# IOTLoRaSmartGreenhouseGateway.net
KiCad netlist of a schematic drawn in Altium Designer
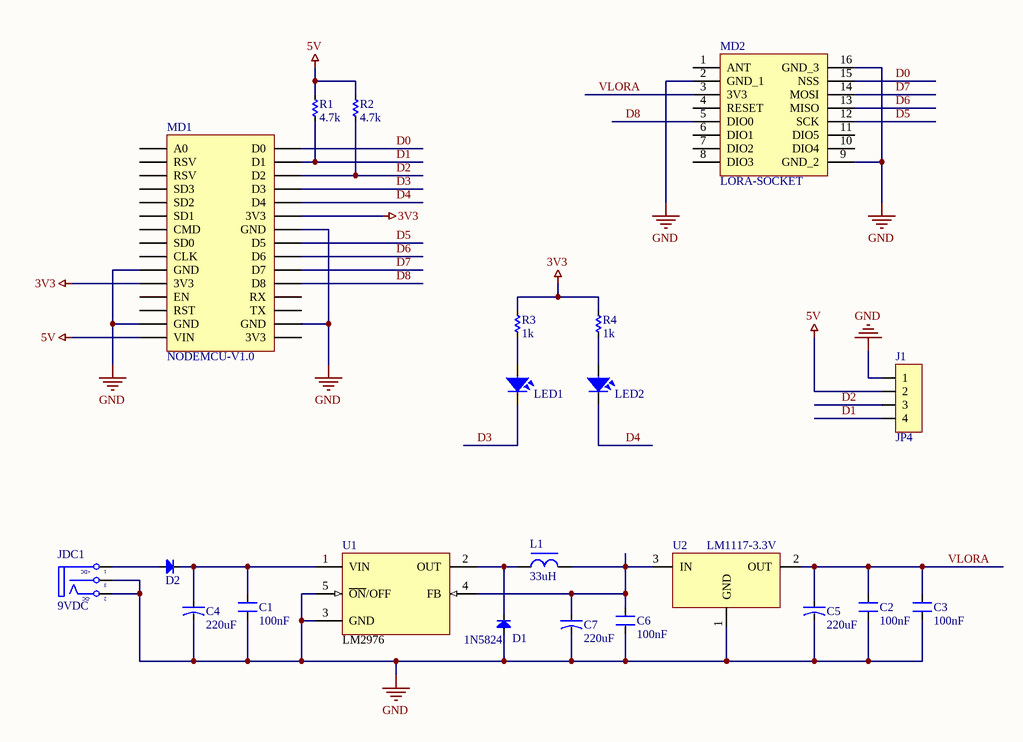
[diagram p0: IOTLoRaSmartGreenhouseGateway.SchDoc]

(export (version "E")
  (design (tool "Eeschema 10.0.6"))
  (components
    (comp (ref "C1") (value "100nF") (footprint "CN1.5") (libsource (lib "LIBRARY") (part "CN")))
    (comp (ref "C2") (value "100nF") (footprint "CN1.5") (libsource (lib "LIBRARY") (part "CN")))
    (comp (ref "C3") (value "100nF") (footprint "CN1.5") (libsource (lib "LIBRARY") (part "CN")))
    (comp (ref "C4")
      (value "220uF")
      (footprint "CA-ALU-8")
      (description "Capacitor (Semiconductor SIM Model)")
      (fields (field (name "PUBLISHER") "Altium Limited"))
      (libsource (lib "LIBRARY") (part "CN-ALU-DIP"))
    )
    (comp (ref "C5")
      (value "220uF")
      (footprint "CA-ALU-8")
      (description "Capacitor (Semiconductor SIM Model)")
      (fields (field (name "PUBLISHER") "Altium Limited"))
      (libsource (lib "LIBRARY") (part "CN-ALU-DIP"))
    )
    (comp (ref "C6") (value "100nF") (footprint "CN1.5") (libsource (lib "LIBRARY") (part "CN")))
    (comp (ref "C7")
      (value "220uF")
      (footprint "CA-ALU-8")
      (description "Capacitor (Semiconductor SIM Model)")
      (fields (field (name "PUBLISHER") "Altium Limited"))
      (libsource (lib "LIBRARY") (part "CN-ALU-DIP"))
    )
    (comp (ref "D1")
      (value "1N5824")
      (footprint "DIO-5A")
      (description "Default Diode")
      (fields (field (name "PUBLISHER") "Altium Limited"))
      (libsource (lib "LIBRARY") (part "Diode"))
    )
    (comp (ref "D2")
      (value "Diode")
      (footprint "DIO-3A")
      (description "Default Diode")
      (fields (field (name "PUBLISHER") "Altium Limited"))
      (libsource (lib "LIBRARY") (part "Diode"))
    )
    (comp (ref "J1")
      (value "JP4")
      (footprint "JP4-D1C")
      (description "WR-PHD 2.54 mm Angled Socket Header")
      (fields
        (field (name "MANUFACTURER") "Würth Elektronik eiSos GmbH")
        (field (name "PARTNO") "613004143121")
        (field (name "CREATED BY") "Karrer Zheng")
      )
      (libsource (lib "LIBRARY") (part "JP4"))
    )
    (comp (ref "JDC1")
      (value "9VDC")
      (footprint "DC0")
      (description "Jac DC input")
      (libsource (lib "LIBRARY") (part "DCIN"))
    )
    (comp (ref "L1")
      (value "33uH")
      (footprint "L-DIP-M-10")
      (description "Inductor")
      (libsource (lib "LIBRARY") (part "L-DIP-1"))
    )
    (comp (ref "LED1")
      (value "LED")
      (footprint "LED-3MM-BLUE")
      (description "LED Single colour Green and Red")
      (libsource (lib "LIBRARY") (part "LED"))
    )
    (comp (ref "LED2")
      (value "LED")
      (footprint "LED-3MM-BLUE")
      (description "LED Single colour Green and Red")
      (libsource (lib "LIBRARY") (part "LED"))
    )
    (comp (ref "MD1")
      (value "NODEMCU-V1.0")
      (footprint "NODEMCU-V1.0")
      (description "KIT NodeMCU v1.0")
      (libsource (lib "phatvu1294_Lib") (part "NODEMCU-V1.0"))
    )
    (comp (ref "MD2")
      (value "LORA-SOCKET")
      (footprint "LORA-SOCKET")
      (description "Socket LoRa RA01 va RA02")
      (libsource (lib "User") (part "LORA-SOCKET"))
    )
    (comp (ref "R1")
      (value "4.7k")
      (footprint "RES-1/4W")
      (description "Res")
      (fields
        (field (name "MANUFACTURER") "Generic Components")
        (field (name "PUBLISHER") "Altium Hobart Technology Centre")
      )
      (libsource (lib "LIBRARY") (part "Res"))
    )
    (comp (ref "R2")
      (value "4.7k")
      (footprint "RES-1/4W")
      (description "Res")
      (fields
        (field (name "MANUFACTURER") "Generic Components")
        (field (name "PUBLISHER") "Altium Hobart Technology Centre")
      )
      (libsource (lib "LIBRARY") (part "Res"))
    )
    (comp (ref "R3")
      (value "1k")
      (footprint "RES-1/4W")
      (description "Res")
      (fields
        (field (name "MANUFACTURER") "Generic Components")
        (field (name "PUBLISHER") "Altium Hobart Technology Centre")
      )
      (libsource (lib "LIBRARY") (part "Res"))
    )
    (comp (ref "R4")
      (value "1k")
      (footprint "RES-1/4W")
      (description "Res")
      (fields
        (field (name "MANUFACTURER") "Generic Components")
        (field (name "PUBLISHER") "Altium Hobart Technology Centre")
      )
      (libsource (lib "LIBRARY") (part "Res"))
    )
    (comp (ref "U1") (value "LM2976") (footprint "TO263") (libsource (lib "LIBRARY") (part "LM2596")))
    (comp (ref "U2")
      (value "LM1117-3.3V")
      (footprint "SOT223")
      (description "800mA Low-Dropout Linear Regulator")
      (fields (field (name "CREATOR") "Nguyen Ba Bien"))
      (libsource (lib "LIBRARY") (part "LM1117"))
    )
  )
  (nets
    (net (code "1") (name "/D0") (class "Default")
      (node (ref "MD1") (pin "D0") (pinfunction "D0_D0") (pintype "passive"))
      (node (ref "MD2") (pin "15") (pinfunction "NSS_15") (pintype "passive"))
    )
    (net (code "2") (name "/D1") (class "Default")
      (node (ref "J1") (pin "4") (pinfunction "4_4") (pintype "passive"))
      (node (ref "MD1") (pin "D1") (pinfunction "D1_D1") (pintype "passive"))
      (node (ref "R1") (pin "2") (pinfunction "2_2") (pintype "passive"))
    )
    (net (code "3") (name "/D2") (class "Default")
      (node (ref "J1") (pin "3") (pinfunction "3_3") (pintype "passive"))
      (node (ref "MD1") (pin "D2") (pinfunction "D2_D2") (pintype "passive"))
      (node (ref "R2") (pin "2") (pinfunction "2_2") (pintype "passive"))
    )
    (net (code "4") (name "/D3") (class "Default")
      (node (ref "LED1") (pin "2") (pinfunction "2_2") (pintype "passive"))
      (node (ref "MD1") (pin "D3") (pinfunction "D3_D3") (pintype "passive"))
    )
    (net (code "5") (name "/D4") (class "Default")
      (node (ref "LED2") (pin "2") (pinfunction "2_2") (pintype "passive"))
      (node (ref "MD1") (pin "D4") (pinfunction "D4_D4") (pintype "passive"))
    )
    (net (code "6") (name "/D5") (class "Default")
      (node (ref "MD1") (pin "D5") (pinfunction "D5_D5") (pintype "passive"))
      (node (ref "MD2") (pin "12") (pinfunction "SCK_12") (pintype "passive"))
    )
    (net (code "7") (name "/D6") (class "Default")
      (node (ref "MD1") (pin "D6") (pinfunction "D6_D6") (pintype "passive"))
      (node (ref "MD2") (pin "13") (pinfunction "MISO_13") (pintype "passive"))
    )
    (net (code "8") (name "/D7") (class "Default")
      (node (ref "MD1") (pin "D7") (pinfunction "D7_D7") (pintype "passive"))
      (node (ref "MD2") (pin "14") (pinfunction "MOSI_14") (pintype "passive"))
    )
    (net (code "9") (name "/D8") (class "Default")
      (node (ref "MD1") (pin "D8") (pinfunction "D8_D8") (pintype "passive"))
      (node (ref "MD2") (pin "5") (pinfunction "DIO0_5") (pintype "passive"))
    )
    (net (code "10") (name "/VLORA") (class "Default")
      (node (ref "C2") (pin "1") (pinfunction "1_1") (pintype "passive"))
      (node (ref "C3") (pin "1") (pinfunction "1_1") (pintype "passive"))
      (node (ref "C5") (pin "1") (pinfunction "1_1") (pintype "passive"))
      (node (ref "MD2") (pin "3") (pinfunction "3V3_3") (pintype "passive"))
      (node (ref "U2") (pin "2") (pinfunction "OUT_2") (pintype "passive"))
    )
    (net (code "11") (name "3V3") (class "Default")
      (node (ref "MD1") (pin "3V3") (pinfunction "3V3_3V3") (pintype "power_in"))
      (node (ref "R3") (pin "1") (pinfunction "1_1") (pintype "passive"))
      (node (ref "R4") (pin "1") (pinfunction "1_1") (pintype "passive"))
    )
    (net (code "12") (name "5V") (class "Default")
      (node (ref "J1") (pin "2") (pinfunction "2_2") (pintype "passive"))
      (node (ref "MD1") (pin "VIN") (pinfunction "VIN_VIN") (pintype "power_in"))
      (node (ref "R1") (pin "1") (pinfunction "1_1") (pintype "passive"))
      (node (ref "R2") (pin "1") (pinfunction "1_1") (pintype "passive"))
    )
    (net (code "13") (name "GND") (class "Default")
      (node (ref "C1") (pin "2") (pinfunction "2_2") (pintype "passive"))
      (node (ref "C2") (pin "2") (pinfunction "2_2") (pintype "passive"))
      (node (ref "C3") (pin "2") (pinfunction "2_2") (pintype "passive"))
      (node (ref "C4") (pin "2") (pinfunction "2_2") (pintype "passive"))
      (node (ref "C5") (pin "2") (pinfunction "2_2") (pintype "passive"))
      (node (ref "C6") (pin "2") (pinfunction "2_2") (pintype "passive"))
      (node (ref "C7") (pin "2") (pinfunction "2_2") (pintype "passive"))
      (node (ref "D1") (pin "1") (pinfunction "A_1") (pintype "passive"))
      (node (ref "J1") (pin "1") (pinfunction "1_1") (pintype "passive"))
      (node (ref "JDC1") (pin "2") (pinfunction "TN_2") (pintype "passive"))
      (node (ref "JDC1") (pin "3") (pinfunction "S_3") (pintype "power_in"))
      (node (ref "MD1") (pin "GND") (pinfunction "GND_GND") (pintype "power_in"))
      (node (ref "MD2") (pin "16") (pinfunction "GND_3_16") (pintype "passive"))
      (node (ref "MD2") (pin "2") (pinfunction "GND_1_2") (pintype "passive"))
      (node (ref "MD2") (pin "9") (pinfunction "GND_2_9") (pintype "passive"))
      (node (ref "U1") (pin "3") (pinfunction "GND_3") (pintype "power_in"))
      (node (ref "U1") (pin "5") (pinfunction "~{ON}/OFF_5") (pintype "input"))
      (node (ref "U2") (pin "1") (pinfunction "GND_1") (pintype "passive"))
    )
    (net (code "14") (name "Net-(D1-K)") (class "Default")
      (node (ref "D1") (pin "2") (pinfunction "K_2") (pintype "passive"))
      (node (ref "L1") (pin "1") (pinfunction "1_1") (pintype "passive"))
      (node (ref "U1") (pin "2") (pinfunction "OUT_2") (pintype "power_in"))
    )
    (net (code "15") (name "Net-(D2-A)") (class "Default")
      (node (ref "D2") (pin "1") (pinfunction "A_1") (pintype "passive"))
      (node (ref "JDC1") (pin "1") (pinfunction "T_1") (pintype "passive"))
    )
    (net (code "16") (name "Net-(D2-K)") (class "Default")
      (node (ref "C1") (pin "1") (pinfunction "1_1") (pintype "passive"))
      (node (ref "C4") (pin "1") (pinfunction "1_1") (pintype "passive"))
      (node (ref "D2") (pin "2") (pinfunction "K_2") (pintype "passive"))
      (node (ref "U1") (pin "1") (pinfunction "VIN_1") (pintype "power_in"))
    )
    (net (code "17") (name "Net-(LED1-Pad1)") (class "Default")
      (node (ref "LED1") (pin "1") (pinfunction "1_1") (pintype "passive"))
      (node (ref "R3") (pin "2") (pinfunction "2_2") (pintype "passive"))
    )
    (net (code "18") (name "Net-(LED2-Pad1)") (class "Default")
      (node (ref "LED2") (pin "1") (pinfunction "1_1") (pintype "passive"))
      (node (ref "R4") (pin "2") (pinfunction "2_2") (pintype "passive"))
    )
    (net (code "19") (name "Net-(U1-FB)") (class "Default")
      (node (ref "C6") (pin "1") (pinfunction "1_1") (pintype "passive"))
      (node (ref "C7") (pin "1") (pinfunction "1_1") (pintype "passive"))
      (node (ref "L1") (pin "2") (pinfunction "2_2") (pintype "passive"))
      (node (ref "U1") (pin "4") (pinfunction "FB_4") (pintype "input"))
      (node (ref "U2") (pin "3") (pinfunction "IN_3") (pintype "passive"))
    )
    (net (code "20") (name "unconnected-(MD1-Pad3V3)") (class "Default")
      (node (ref "MD1") (pin "3V3") (pinfunction "3V3_3V3") (pintype "power_in"))
    )
    (net (code "21") (name "unconnected-(MD1-PadA0)") (class "Default")
      (node (ref "MD1") (pin "A0") (pinfunction "A0_A0") (pintype "passive"))
    )
    (net (code "22") (name "unconnected-(MD1-PadCLK)") (class "Default")
      (node (ref "MD1") (pin "CLK") (pinfunction "CLK_CLK") (pintype "passive"))
    )
    (net (code "23") (name "unconnected-(MD1-PadCMD)") (class "Default")
      (node (ref "MD1") (pin "CMD") (pinfunction "CMD_CMD") (pintype "passive"))
    )
    (net (code "24") (name "unconnected-(MD1-PadEN)") (class "Default")
      (node (ref "MD1") (pin "EN") (pinfunction "EN_EN") (pintype "passive"))
    )
    (net (code "25") (name "unconnected-(MD1-PadRST)") (class "Default")
      (node (ref "MD1") (pin "RST") (pinfunction "RST_RST") (pintype "passive"))
    )
    (net (code "26") (name "unconnected-(MD1-PadRSV)") (class "Default")
      (node (ref "MD1") (pin "RSV") (pinfunction "RSV_RSV") (pintype "passive"))
    )
    (net (code "27") (name "unconnected-(MD1-PadRSV)_1") (class "Default")
      (node (ref "MD1") (pin "RSV") (pinfunction "RSV_RSV") (pintype "passive"))
    )
    (net (code "28") (name "unconnected-(MD1-PadRX)") (class "Default")
      (node (ref "MD1") (pin "RX") (pinfunction "RX_RX") (pintype "passive"))
    )
    (net (code "29") (name "unconnected-(MD1-PadSD0)") (class "Default")
      (node (ref "MD1") (pin "SD0") (pinfunction "SD0_SD0") (pintype "passive"))
    )
    (net (code "30") (name "unconnected-(MD1-PadSD1)") (class "Default")
      (node (ref "MD1") (pin "SD1") (pinfunction "SD1_SD1") (pintype "passive"))
    )
    (net (code "31") (name "unconnected-(MD1-PadSD2)") (class "Default")
      (node (ref "MD1") (pin "SD2") (pinfunction "SD2_SD2") (pintype "passive"))
    )
    (net (code "32") (name "unconnected-(MD1-PadSD3)") (class "Default")
      (node (ref "MD1") (pin "SD3") (pinfunction "SD3_SD3") (pintype "passive"))
    )
    (net (code "33") (name "unconnected-(MD1-PadTX)") (class "Default")
      (node (ref "MD1") (pin "TX") (pinfunction "TX_TX") (pintype "passive"))
    )
    (net (code "34") (name "unconnected-(MD2-ANT-Pad1)") (class "Default")
      (node (ref "MD2") (pin "1") (pinfunction "ANT_1") (pintype "passive"))
    )
    (net (code "35") (name "unconnected-(MD2-DIO1-Pad6)") (class "Default")
      (node (ref "MD2") (pin "6") (pinfunction "DIO1_6") (pintype "passive"))
    )
    (net (code "36") (name "unconnected-(MD2-DIO2-Pad7)") (class "Default")
      (node (ref "MD2") (pin "7") (pinfunction "DIO2_7") (pintype "passive"))
    )
    (net (code "37") (name "unconnected-(MD2-DIO3-Pad8)") (class "Default")
      (node (ref "MD2") (pin "8") (pinfunction "DIO3_8") (pintype "passive"))
    )
    (net (code "38") (name "unconnected-(MD2-DIO4-Pad10)") (class "Default")
      (node (ref "MD2") (pin "10") (pinfunction "DIO4_10") (pintype "passive"))
    )
    (net (code "39") (name "unconnected-(MD2-DIO5-Pad11)") (class "Default")
      (node (ref "MD2") (pin "11") (pinfunction "DIO5_11") (pintype "passive"))
    )
    (net (code "40") (name "unconnected-(MD2-RESET-Pad4)") (class "Default")
      (node (ref "MD2") (pin "4") (pinfunction "RESET_4") (pintype "passive"))
    )
  )
)
